# Vibration.net
KiCad netlist of a schematic drawn in Altium Designer
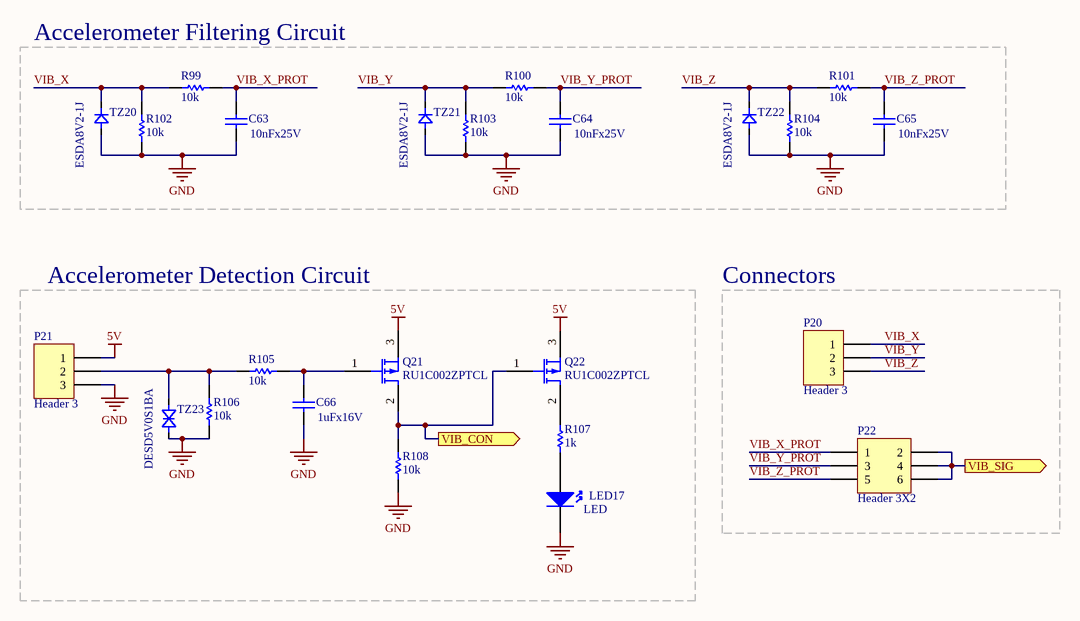
[diagram p0: Vibration.SchDoc]

(export (version "E")
  (design (tool "Eeschema 10.0.6"))
  (components
    (comp (ref "C63")
      (value "10nFx25V")
      (footprint "DISC-0805")
      (description "Capacitor")
      (libsource (lib "IntLib") (part "Cap"))
    )
    (comp (ref "C64")
      (value "10nFx25V")
      (footprint "DISC-0805")
      (description "Capacitor")
      (libsource (lib "IntLib") (part "Cap"))
    )
    (comp (ref "C65")
      (value "10nFx25V")
      (footprint "DISC-0805")
      (description "Capacitor")
      (libsource (lib "IntLib") (part "Cap"))
    )
    (comp (ref "C66")
      (value "1uFx16V")
      (footprint "DISC-0805")
      (description "Capacitor")
      (libsource (lib "IntLib") (part "Cap"))
    )
    (comp (ref "LED17") (value "LED") (footprint "DISC-LED-0.1-PTH") (libsource (lib "IntLib") (part "LED")))
    (comp (ref "P20")
      (value "Header 3")
      (footprint "CON-BORNE-3")
      (description "Header, 3-Pin")
      (fields (field (name "PUBLISHER") "Altium Limited"))
      (libsource (lib "IntLib") (part "Header 3"))
    )
    (comp (ref "P21")
      (value "Header 3")
      (footprint "CON-BORNE-3")
      (description "Header, 3-Pin")
      (fields (field (name "PUBLISHER") "Altium Limited"))
      (libsource (lib "IntLib") (part "Header 3"))
    )
    (comp (ref "P22")
      (value "Header 3X2")
      (footprint "CON-HEADER-2X3-PTH")
      (description "Header, 3-Pin, Dual row")
      (fields (field (name "PUBLISHER") "Altium Limited"))
      (libsource (lib "IntLib") (part "Header 3X2"))
    )
    (comp (ref "Q21")
      (value "RU1C002ZPTCL")
      (footprint "DISC-SOT-23")
      (description "P-Channel MOSFET")
      (libsource (lib "IntLib") (part "Transistor-PMOS"))
    )
    (comp (ref "Q22")
      (value "RU1C002ZPTCL")
      (footprint "DISC-SOT-23")
      (description "P-Channel MOSFET")
      (libsource (lib "IntLib") (part "Transistor-PMOS"))
    )
    (comp (ref "R99")
      (value "10k")
      (footprint "DISC-0805")
      (description "Resistor")
      (libsource (lib "IntLib") (part "Res"))
    )
    (comp (ref "R100")
      (value "10k")
      (footprint "DISC-0805")
      (description "Resistor")
      (libsource (lib "IntLib") (part "Res"))
    )
    (comp (ref "R101")
      (value "10k")
      (footprint "DISC-0805")
      (description "Resistor")
      (libsource (lib "IntLib") (part "Res"))
    )
    (comp (ref "R102")
      (value "10k")
      (footprint "DISC-0805")
      (description "Resistor")
      (libsource (lib "IntLib") (part "Res"))
    )
    (comp (ref "R103")
      (value "10k")
      (footprint "DISC-0805")
      (description "Resistor")
      (libsource (lib "IntLib") (part "Res"))
    )
    (comp (ref "R104")
      (value "10k")
      (footprint "DISC-0805")
      (description "Resistor")
      (libsource (lib "IntLib") (part "Res"))
    )
    (comp (ref "R105")
      (value "10k")
      (footprint "DISC-0805")
      (description "Resistor")
      (libsource (lib "IntLib") (part "Res"))
    )
    (comp (ref "R106")
      (value "10k")
      (footprint "DISC-0805")
      (description "Resistor")
      (libsource (lib "IntLib") (part "Res"))
    )
    (comp (ref "R107")
      (value "1k")
      (footprint "DISC-0805")
      (description "Resistor")
      (libsource (lib "IntLib") (part "Res"))
    )
    (comp (ref "R108")
      (value "10k")
      (footprint "DISC-0805")
      (description "Resistor")
      (libsource (lib "IntLib") (part "Res"))
    )
    (comp (ref "TZ20")
      (value "ESDA8V2-1J")
      (footprint "DISC-SOD-323")
      (description "TVZ-Unidirectional")
      (libsource (lib "IntLib") (part "TVZ-Unidirectional"))
    )
    (comp (ref "TZ21")
      (value "ESDA8V2-1J")
      (footprint "DISC-SOD-323")
      (description "TVZ-Unidirectional")
      (libsource (lib "IntLib") (part "TVZ-Unidirectional"))
    )
    (comp (ref "TZ22")
      (value "ESDA8V2-1J")
      (footprint "DISC-SOD-323")
      (description "TVZ-Unidirectional")
      (libsource (lib "IntLib") (part "TVZ-Unidirectional"))
    )
    (comp (ref "TZ23")
      (value "DESD5V0S1BA")
      (footprint "DISC-SOD-323")
      (description "TVZ-Bi-Directional")
      (libsource (lib "IntLib") (part "TVZ-Bi-Directional"))
    )
  )
  (nets
    (net (code "1") (name "/VIB_CON") (class "Default")
      (node (ref "Q21") (pin "2") (pinfunction "D_2") (pintype "passive"))
      (node (ref "Q22") (pin "1") (pinfunction "G_1") (pintype "passive"))
      (node (ref "R108") (pin "2") (pinfunction "2_2") (pintype "passive"))
    )
    (net (code "2") (name "/VIB_SIG") (class "Default")
      (node (ref "P22") (pin "2") (pinfunction "2_2") (pintype "passive"))
      (node (ref "P22") (pin "4") (pinfunction "4_4") (pintype "passive"))
      (node (ref "P22") (pin "6") (pinfunction "6_6") (pintype "passive"))
    )
    (net (code "3") (name "/VIB_X") (class "Default")
      (node (ref "P20") (pin "1") (pinfunction "1_1") (pintype "passive"))
      (node (ref "R102") (pin "1") (pinfunction "1_1") (pintype "passive"))
      (node (ref "R99") (pin "2") (pinfunction "2_2") (pintype "passive"))
      (node (ref "TZ20") (pin "2") (pinfunction "C_2") (pintype "passive"))
    )
    (net (code "4") (name "/VIB_X_PROT") (class "Default")
      (node (ref "C63") (pin "2") (pinfunction "2_2") (pintype "passive"))
      (node (ref "P22") (pin "1") (pinfunction "1_1") (pintype "passive"))
      (node (ref "R99") (pin "1") (pinfunction "1_1") (pintype "passive"))
    )
    (net (code "5") (name "/VIB_Y") (class "Default")
      (node (ref "P20") (pin "2") (pinfunction "2_2") (pintype "passive"))
      (node (ref "R100") (pin "2") (pinfunction "2_2") (pintype "passive"))
      (node (ref "R103") (pin "1") (pinfunction "1_1") (pintype "passive"))
      (node (ref "TZ21") (pin "2") (pinfunction "C_2") (pintype "passive"))
    )
    (net (code "6") (name "/VIB_Y_PROT") (class "Default")
      (node (ref "C64") (pin "2") (pinfunction "2_2") (pintype "passive"))
      (node (ref "P22") (pin "3") (pinfunction "3_3") (pintype "passive"))
      (node (ref "R100") (pin "1") (pinfunction "1_1") (pintype "passive"))
    )
    (net (code "7") (name "/VIB_Z") (class "Default")
      (node (ref "P20") (pin "3") (pinfunction "3_3") (pintype "passive"))
      (node (ref "R101") (pin "2") (pinfunction "2_2") (pintype "passive"))
      (node (ref "R104") (pin "1") (pinfunction "1_1") (pintype "passive"))
      (node (ref "TZ22") (pin "2") (pinfunction "C_2") (pintype "passive"))
    )
    (net (code "8") (name "/VIB_Z_PROT") (class "Default")
      (node (ref "C65") (pin "2") (pinfunction "2_2") (pintype "passive"))
      (node (ref "P22") (pin "5") (pinfunction "5_5") (pintype "passive"))
      (node (ref "R101") (pin "1") (pinfunction "1_1") (pintype "passive"))
    )
    (net (code "9") (name "5V") (class "Default")
      (node (ref "P21") (pin "1") (pinfunction "1_1") (pintype "passive"))
      (node (ref "Q21") (pin "3") (pinfunction "S_3") (pintype "passive"))
      (node (ref "Q22") (pin "3") (pinfunction "S_3") (pintype "passive"))
    )
    (net (code "10") (name "GND") (class "Default")
      (node (ref "C63") (pin "1") (pinfunction "1_1") (pintype "passive"))
      (node (ref "C64") (pin "1") (pinfunction "1_1") (pintype "passive"))
      (node (ref "C65") (pin "1") (pinfunction "1_1") (pintype "passive"))
      (node (ref "C66") (pin "1") (pinfunction "1_1") (pintype "passive"))
      (node (ref "LED17") (pin "2") (pinfunction "K_2") (pintype "passive"))
      (node (ref "P21") (pin "3") (pinfunction "3_3") (pintype "passive"))
      (node (ref "R102") (pin "2") (pinfunction "2_2") (pintype "passive"))
      (node (ref "R103") (pin "2") (pinfunction "2_2") (pintype "passive"))
      (node (ref "R104") (pin "2") (pinfunction "2_2") (pintype "passive"))
      (node (ref "R106") (pin "2") (pinfunction "2_2") (pintype "passive"))
      (node (ref "R108") (pin "1") (pinfunction "1_1") (pintype "passive"))
      (node (ref "TZ20") (pin "1") (pinfunction "A_1") (pintype "passive"))
      (node (ref "TZ21") (pin "1") (pinfunction "A_1") (pintype "passive"))
      (node (ref "TZ22") (pin "1") (pinfunction "A_1") (pintype "passive"))
      (node (ref "TZ23") (pin "1") (pinfunction "A_1") (pintype "passive"))
    )
    (net (code "11") (name "Net-(LED17-A)") (class "Default")
      (node (ref "LED17") (pin "1") (pinfunction "A_1") (pintype "passive"))
      (node (ref "R107") (pin "1") (pinfunction "1_1") (pintype "passive"))
    )
    (net (code "12") (name "Net-(Q21-G)") (class "Default")
      (node (ref "C66") (pin "2") (pinfunction "2_2") (pintype "passive"))
      (node (ref "Q21") (pin "1") (pinfunction "G_1") (pintype "passive"))
      (node (ref "R105") (pin "2") (pinfunction "2_2") (pintype "passive"))
    )
    (net (code "13") (name "Net-(Q22-D)") (class "Default")
      (node (ref "Q22") (pin "2") (pinfunction "D_2") (pintype "passive"))
      (node (ref "R107") (pin "2") (pinfunction "2_2") (pintype "passive"))
    )
    (net (code "14") (name "Net-(TZ23-K)") (class "Default")
      (node (ref "P21") (pin "2") (pinfunction "2_2") (pintype "passive"))
      (node (ref "R105") (pin "1") (pinfunction "1_1") (pintype "passive"))
      (node (ref "R106") (pin "1") (pinfunction "1_1") (pintype "passive"))
      (node (ref "TZ23") (pin "2") (pinfunction "K_2") (pintype "passive"))
    )
  )
)
